# AddonDragon.net
KiCad netlist of a schematic drawn in EasyEDA Pro
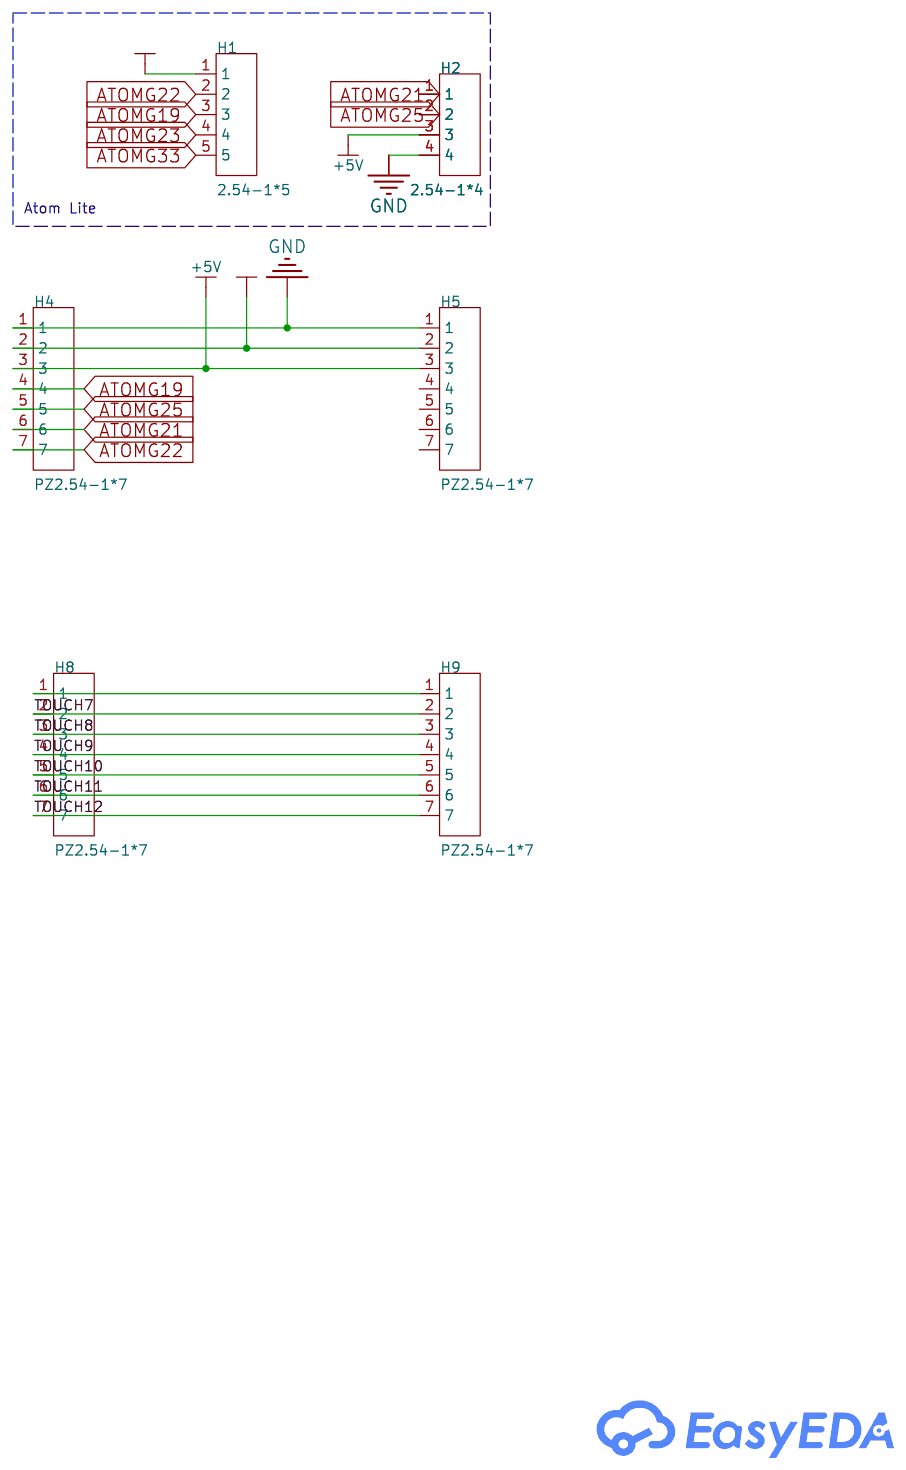
[diagram p0: schematic sheet]

(export (version "E")
  (design (tool "Eeschema 10.0.6"))
  (components
    (comp (ref "H1")
      (value "2.54-1*5")
      (footprint "easyedapro:HDR-TH_5P-P2.54-V-M")
      (description "Pin Structure:1x5P Pitch:2.54mm Number of Rows:Single Row Number of Pins:5P")
      (fields (field (name "Manufacturer") "ZHOURI(洲日)"))
      (libsource (lib "easyedapro") (part "2.54-1*5"))
    )
    (comp (ref "H2")
      (value "2.54-1*4")
      (footprint "easyedapro:HDR-TH_4P-P2.54-V-M-1")
      (description "Pin Structure:1x4P Pitch:2.54mm Number of Rows:Single Row Number of Pins:4P")
      (fields (field (name "Manufacturer") "ZHOURI(洲日)"))
      (libsource (lib "easyedapro") (part "2.54-1*4"))
    )
    (comp (ref "H4")
      (value "PZ2.54-1*7")
      (footprint "easyedapro:HDR-TH_7P-P2.54-V-M")
      (fields (field (name "Manufacturer") "ZHOURI(洲日)"))
      (libsource (lib "easyedapro") (part "PZ2.54-1*7"))
    )
    (comp (ref "H5")
      (value "PZ2.54-1*7")
      (footprint "easyedapro:HDR-TH_7P-P2.54-V-M")
      (fields (field (name "Manufacturer") "ZHOURI(洲日)"))
      (libsource (lib "easyedapro") (part "PZ2.54-1*7"))
    )
    (comp (ref "H8")
      (value "PZ2.54-1*7")
      (footprint "easyedapro:HDR-TH_7P-P2.54-V-M")
      (fields (field (name "Manufacturer") "ZHOURI(洲日)"))
      (libsource (lib "easyedapro") (part "PZ2.54-1*7"))
    )
    (comp (ref "H9")
      (value "PZ2.54-1*7")
      (footprint "easyedapro:HDR-TH_7P-P2.54-V-M")
      (fields (field (name "Manufacturer") "ZHOURI(洲日)"))
      (libsource (lib "easyedapro") (part "PZ2.54-1*7"))
    )
  )
  (nets
    (net (code "1") (name "+5V") (class "Default")
      (node (ref "H2") (pin "3") (pinfunction "3_3") (pintype "unspecified"))
      (node (ref "H4") (pin "3") (pinfunction "3_3") (pintype "unspecified"))
      (node (ref "H5") (pin "3") (pinfunction "3_3") (pintype "unspecified"))
    )
    (net (code "2") (name "/TOUCH7") (class "Default")
      (node (ref "H8") (pin "2") (pinfunction "2_2") (pintype "unspecified"))
      (node (ref "H9") (pin "2") (pinfunction "2_2") (pintype "unspecified"))
    )
    (net (code "3") (name "/TOUCH8") (class "Default")
      (node (ref "H8") (pin "3") (pinfunction "3_3") (pintype "unspecified"))
      (node (ref "H9") (pin "3") (pinfunction "3_3") (pintype "unspecified"))
    )
    (net (code "4") (name "/TOUCH9") (class "Default")
      (node (ref "H8") (pin "4") (pinfunction "4_4") (pintype "unspecified"))
      (node (ref "H9") (pin "4") (pinfunction "4_4") (pintype "unspecified"))
    )
    (net (code "5") (name "/TOUCH10") (class "Default")
      (node (ref "H8") (pin "5") (pinfunction "5_5") (pintype "unspecified"))
      (node (ref "H9") (pin "5") (pinfunction "5_5") (pintype "unspecified"))
    )
    (net (code "6") (name "/TOUCH11") (class "Default")
      (node (ref "H8") (pin "6") (pinfunction "6_6") (pintype "unspecified"))
      (node (ref "H9") (pin "6") (pinfunction "6_6") (pintype "unspecified"))
    )
    (net (code "7") (name "/TOUCH12") (class "Default")
      (node (ref "H8") (pin "7") (pinfunction "7_7") (pintype "unspecified"))
      (node (ref "H9") (pin "7") (pinfunction "7_7") (pintype "unspecified"))
    )
    (net (code "8") (name "3V3") (class "Default")
      (node (ref "H1") (pin "1") (pinfunction "1_1") (pintype "unspecified"))
      (node (ref "H4") (pin "2") (pinfunction "2_2") (pintype "unspecified"))
      (node (ref "H5") (pin "2") (pinfunction "2_2") (pintype "unspecified"))
    )
    (net (code "9") (name "ATOMG19") (class "Default")
      (node (ref "H1") (pin "3") (pinfunction "3_3") (pintype "unspecified"))
      (node (ref "H4") (pin "4") (pinfunction "4_4") (pintype "unspecified"))
    )
    (net (code "10") (name "ATOMG21") (class "Default")
      (node (ref "H2") (pin "1") (pinfunction "1_1") (pintype "unspecified"))
      (node (ref "H4") (pin "6") (pinfunction "6_6") (pintype "unspecified"))
    )
    (net (code "11") (name "ATOMG22") (class "Default")
      (node (ref "H1") (pin "2") (pinfunction "2_2") (pintype "unspecified"))
      (node (ref "H4") (pin "7") (pinfunction "7_7") (pintype "unspecified"))
    )
    (net (code "12") (name "ATOMG23") (class "Default")
      (node (ref "H1") (pin "4") (pinfunction "4_4") (pintype "unspecified"))
    )
    (net (code "13") (name "ATOMG25") (class "Default")
      (node (ref "H2") (pin "2") (pinfunction "2_2") (pintype "unspecified"))
      (node (ref "H4") (pin "5") (pinfunction "5_5") (pintype "unspecified"))
    )
    (net (code "14") (name "ATOMG33") (class "Default")
      (node (ref "H1") (pin "5") (pinfunction "5_5") (pintype "unspecified"))
    )
    (net (code "15") (name "GND") (class "Default")
      (node (ref "H2") (pin "4") (pinfunction "4_4") (pintype "unspecified"))
      (node (ref "H4") (pin "1") (pinfunction "1_1") (pintype "unspecified"))
      (node (ref "H5") (pin "1") (pinfunction "1_1") (pintype "unspecified"))
    )
    (net (code "16") (name "Net-(H8-Pad1)") (class "Default")
      (node (ref "H8") (pin "1") (pinfunction "1_1") (pintype "unspecified"))
      (node (ref "H9") (pin "1") (pinfunction "1_1") (pintype "unspecified"))
    )
    (net (code "17") (name "unconnected-(H5-Pad4)") (class "Default")
      (node (ref "H5") (pin "4") (pinfunction "4_4") (pintype "unspecified"))
    )
    (net (code "18") (name "unconnected-(H5-Pad5)") (class "Default")
      (node (ref "H5") (pin "5") (pinfunction "5_5") (pintype "unspecified"))
    )
    (net (code "19") (name "unconnected-(H5-Pad6)") (class "Default")
      (node (ref "H5") (pin "6") (pinfunction "6_6") (pintype "unspecified"))
    )
    (net (code "20") (name "unconnected-(H5-Pad7)") (class "Default")
      (node (ref "H5") (pin "7") (pinfunction "7_7") (pintype "unspecified"))
    )
  )
)
